# Adapter.net
KiCad netlist of a schematic drawn in Altium Designer
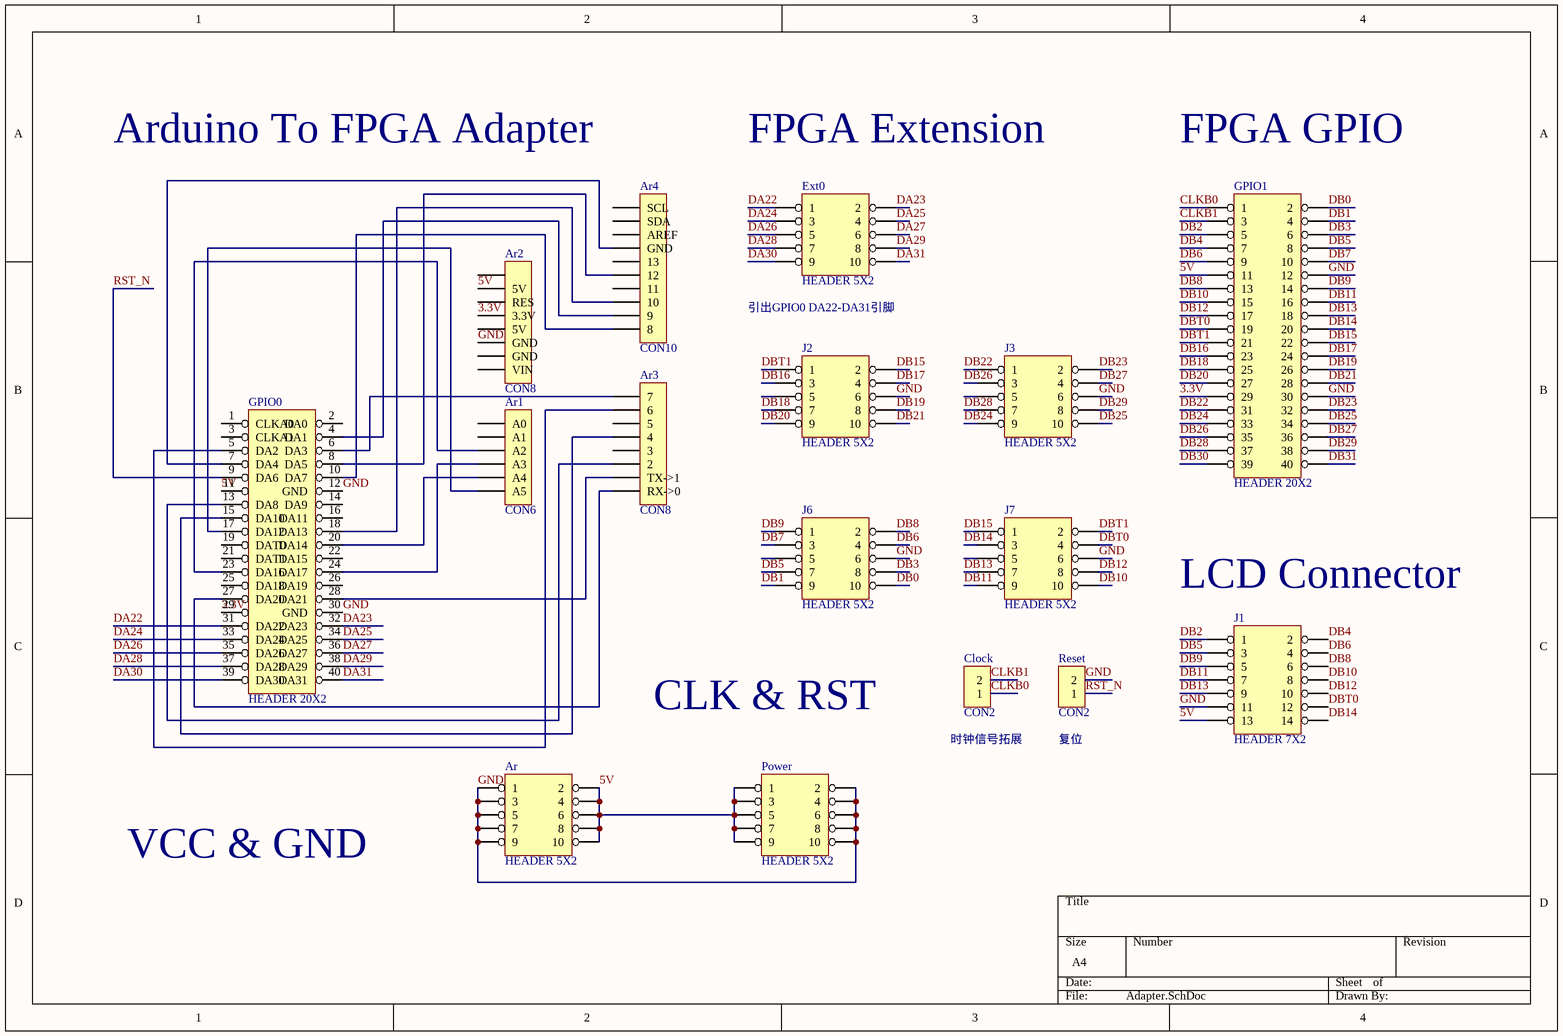
[diagram p0: Adapter.SchDoc]

(export (version "E")
  (design (tool "Eeschema 10.0.6"))
  (components
    (comp (ref "Ar")
      (value "HEADER 5X2")
      (footprint "HDR2X5")
      (libsource (lib "Miscellaneous Devices") (part "HEADER 5X2"))
    )
    (comp (ref "Ar1") (value "CON6") (footprint "HDR1X6") (libsource (lib "常用元件库") (part "CON6")))
    (comp (ref "Ar2") (value "CON8") (footprint "HDR1X8") (libsource (lib "常用元件库") (part "CON8")))
    (comp (ref "Ar3") (value "CON8") (footprint "HDR1X8") (libsource (lib "常用元件库") (part "CON8")))
    (comp (ref "Ar4") (value "CON10") (footprint "HDR1X10") (libsource (lib "常用元件库") (part "CON10")))
    (comp (ref "Clock")
      (value "CON2")
      (footprint "HDR1X2")
      (description "Connector")
      (libsource (lib "Miscellaneous Devices") (part "CON2"))
    )
    (comp (ref "Ext0")
      (value "HEADER 5X2")
      (footprint "HDR2X5")
      (libsource (lib "Miscellaneous Devices") (part "HEADER 5X2"))
    )
    (comp (ref "GPIO0")
      (value "HEADER 20X2")
      (footprint "Miscellaneous Connectors:HDR2X20")
      (libsource (lib "Miscellaneous Devices") (part "HEADER 20X2"))
    )
    (comp (ref "GPIO1")
      (value "HEADER 20X2")
      (footprint "Miscellaneous Connectors:HDR2X20")
      (libsource (lib "") (part "HEADER 20X2_1"))
    )
    (comp (ref "J1")
      (value "HEADER 7X2")
      (footprint "HDR2X7")
      (libsource (lib "Miscellaneous Devices") (part "HEADER 7X2"))
    )
    (comp (ref "J2")
      (value "HEADER 5X2")
      (footprint "HDR2X5")
      (libsource (lib "Miscellaneous Devices") (part "HEADER 5X2"))
    )
    (comp (ref "J3")
      (value "HEADER 5X2")
      (footprint "HDR2X5")
      (libsource (lib "Miscellaneous Devices") (part "HEADER 5X2"))
    )
    (comp (ref "J6")
      (value "HEADER 5X2")
      (footprint "HDR2X5")
      (libsource (lib "Miscellaneous Devices") (part "HEADER 5X2"))
    )
    (comp (ref "J7")
      (value "HEADER 5X2")
      (footprint "HDR2X5")
      (libsource (lib "Miscellaneous Devices") (part "HEADER 5X2"))
    )
    (comp (ref "Power")
      (value "HEADER 5X2")
      (footprint "HDR2X5")
      (libsource (lib "Miscellaneous Devices") (part "HEADER 5X2"))
    )
    (comp (ref "Reset")
      (value "CON2")
      (footprint "HDR1X2")
      (description "Connector")
      (libsource (lib "Miscellaneous Devices") (part "CON2"))
    )
  )
  (nets
    (net (code "1") (name "/3.3V") (class "Default")
      (node (ref "Ar2") (pin "4") (pinfunction "3.3V_4") (pintype "passive"))
      (node (ref "GPIO0") (pin "29") (pinfunction "29_29") (pintype "passive"))
      (node (ref "GPIO1") (pin "29") (pinfunction "29_29") (pintype "passive"))
    )
    (net (code "2") (name "/5V") (class "Default")
      (node (ref "Ar") (pin "10") (pinfunction "10_10") (pintype "passive"))
      (node (ref "Ar") (pin "2") (pinfunction "2_2") (pintype "passive"))
      (node (ref "Ar") (pin "4") (pinfunction "4_4") (pintype "passive"))
      (node (ref "Ar") (pin "6") (pinfunction "6_6") (pintype "passive"))
      (node (ref "Ar") (pin "8") (pinfunction "8_8") (pintype "passive"))
      (node (ref "Ar2") (pin "2") (pinfunction "5V_2") (pintype "passive"))
      (node (ref "GPIO0") (pin "11") (pinfunction "11_11") (pintype "passive"))
      (node (ref "GPIO1") (pin "11") (pinfunction "11_11") (pintype "passive"))
      (node (ref "J1") (pin "13") (pinfunction "13_13") (pintype "passive"))
      (node (ref "Power") (pin "1") (pinfunction "1_1") (pintype "passive"))
      (node (ref "Power") (pin "3") (pinfunction "3_3") (pintype "passive"))
      (node (ref "Power") (pin "5") (pinfunction "5_5") (pintype "passive"))
      (node (ref "Power") (pin "7") (pinfunction "7_7") (pintype "passive"))
      (node (ref "Power") (pin "9") (pinfunction "9_9") (pintype "passive"))
    )
    (net (code "3") (name "/CLKB0") (class "Default")
      (node (ref "Clock") (pin "1") (pinfunction "1_1") (pintype "passive"))
      (node (ref "GPIO1") (pin "1") (pinfunction "1_1") (pintype "passive"))
    )
    (net (code "4") (name "/CLKB1") (class "Default")
      (node (ref "Clock") (pin "2") (pinfunction "2_2") (pintype "passive"))
      (node (ref "GPIO1") (pin "3") (pinfunction "3_3") (pintype "passive"))
    )
    (net (code "5") (name "/DA22") (class "Default")
      (node (ref "Ext0") (pin "1") (pinfunction "1_1") (pintype "passive"))
      (node (ref "GPIO0") (pin "31") (pinfunction "DA22_31") (pintype "passive"))
    )
    (net (code "6") (name "/DA23") (class "Default")
      (node (ref "Ext0") (pin "2") (pinfunction "2_2") (pintype "passive"))
      (node (ref "GPIO0") (pin "32") (pinfunction "DA23_32") (pintype "passive"))
    )
    (net (code "7") (name "/DA24") (class "Default")
      (node (ref "Ext0") (pin "3") (pinfunction "3_3") (pintype "passive"))
      (node (ref "GPIO0") (pin "33") (pinfunction "DA24_33") (pintype "passive"))
    )
    (net (code "8") (name "/DA25") (class "Default")
      (node (ref "Ext0") (pin "4") (pinfunction "4_4") (pintype "passive"))
      (node (ref "GPIO0") (pin "34") (pinfunction "DA25_34") (pintype "passive"))
    )
    (net (code "9") (name "/DA26") (class "Default")
      (node (ref "Ext0") (pin "5") (pinfunction "5_5") (pintype "passive"))
      (node (ref "GPIO0") (pin "35") (pinfunction "DA26_35") (pintype "passive"))
    )
    (net (code "10") (name "/DA27") (class "Default")
      (node (ref "Ext0") (pin "6") (pinfunction "6_6") (pintype "passive"))
      (node (ref "GPIO0") (pin "36") (pinfunction "DA27_36") (pintype "passive"))
    )
    (net (code "11") (name "/DA28") (class "Default")
      (node (ref "Ext0") (pin "7") (pinfunction "7_7") (pintype "passive"))
      (node (ref "GPIO0") (pin "37") (pinfunction "DA28_37") (pintype "passive"))
    )
    (net (code "12") (name "/DA29") (class "Default")
      (node (ref "Ext0") (pin "8") (pinfunction "8_8") (pintype "passive"))
      (node (ref "GPIO0") (pin "38") (pinfunction "DA29_38") (pintype "passive"))
    )
    (net (code "13") (name "/DA30") (class "Default")
      (node (ref "Ext0") (pin "9") (pinfunction "9_9") (pintype "passive"))
      (node (ref "GPIO0") (pin "39") (pinfunction "DA30_39") (pintype "passive"))
    )
    (net (code "14") (name "/DA31") (class "Default")
      (node (ref "Ext0") (pin "10") (pinfunction "10_10") (pintype "passive"))
      (node (ref "GPIO0") (pin "40") (pinfunction "DA31_40") (pintype "passive"))
    )
    (net (code "15") (name "/DB0") (class "Default")
      (node (ref "GPIO1") (pin "2") (pinfunction "2_2") (pintype "passive"))
      (node (ref "J6") (pin "10") (pinfunction "10_10") (pintype "passive"))
    )
    (net (code "16") (name "/DB1") (class "Default")
      (node (ref "GPIO1") (pin "4") (pinfunction "4_4") (pintype "passive"))
      (node (ref "J6") (pin "9") (pinfunction "9_9") (pintype "passive"))
    )
    (net (code "17") (name "/DB2") (class "Default")
      (node (ref "GPIO1") (pin "5") (pinfunction "5_5") (pintype "passive"))
      (node (ref "J1") (pin "1") (pinfunction "1_1") (pintype "passive"))
    )
    (net (code "18") (name "/DB3") (class "Default")
      (node (ref "GPIO1") (pin "6") (pinfunction "6_6") (pintype "passive"))
      (node (ref "J6") (pin "8") (pinfunction "8_8") (pintype "passive"))
    )
    (net (code "19") (name "/DB4") (class "Default")
      (node (ref "GPIO1") (pin "7") (pinfunction "7_7") (pintype "passive"))
      (node (ref "J1") (pin "2") (pinfunction "2_2") (pintype "passive"))
    )
    (net (code "20") (name "/DB5") (class "Default")
      (node (ref "GPIO1") (pin "8") (pinfunction "8_8") (pintype "passive"))
      (node (ref "J1") (pin "3") (pinfunction "3_3") (pintype "passive"))
      (node (ref "J6") (pin "7") (pinfunction "7_7") (pintype "passive"))
    )
    (net (code "21") (name "/DB6") (class "Default")
      (node (ref "GPIO1") (pin "9") (pinfunction "9_9") (pintype "passive"))
      (node (ref "J1") (pin "4") (pinfunction "4_4") (pintype "passive"))
      (node (ref "J6") (pin "4") (pinfunction "4_4") (pintype "passive"))
    )
    (net (code "22") (name "/DB7") (class "Default")
      (node (ref "GPIO1") (pin "10") (pinfunction "10_10") (pintype "passive"))
      (node (ref "J6") (pin "3") (pinfunction "3_3") (pintype "passive"))
    )
    (net (code "23") (name "/DB8") (class "Default")
      (node (ref "GPIO1") (pin "13") (pinfunction "13_13") (pintype "passive"))
      (node (ref "J1") (pin "6") (pinfunction "6_6") (pintype "passive"))
      (node (ref "J6") (pin "2") (pinfunction "2_2") (pintype "passive"))
    )
    (net (code "24") (name "/DB9") (class "Default")
      (node (ref "GPIO1") (pin "14") (pinfunction "14_14") (pintype "passive"))
      (node (ref "J1") (pin "5") (pinfunction "5_5") (pintype "passive"))
      (node (ref "J6") (pin "1") (pinfunction "1_1") (pintype "passive"))
    )
    (net (code "25") (name "/DB10") (class "Default")
      (node (ref "GPIO1") (pin "15") (pinfunction "15_15") (pintype "passive"))
      (node (ref "J1") (pin "8") (pinfunction "8_8") (pintype "passive"))
      (node (ref "J7") (pin "10") (pinfunction "10_10") (pintype "passive"))
    )
    (net (code "26") (name "/DB11") (class "Default")
      (node (ref "GPIO1") (pin "16") (pinfunction "16_16") (pintype "passive"))
      (node (ref "J1") (pin "7") (pinfunction "7_7") (pintype "passive"))
      (node (ref "J7") (pin "9") (pinfunction "9_9") (pintype "passive"))
    )
    (net (code "27") (name "/DB12") (class "Default")
      (node (ref "GPIO1") (pin "17") (pinfunction "17_17") (pintype "passive"))
      (node (ref "J1") (pin "10") (pinfunction "10_10") (pintype "passive"))
      (node (ref "J7") (pin "8") (pinfunction "8_8") (pintype "passive"))
    )
    (net (code "28") (name "/DB13") (class "Default")
      (node (ref "GPIO1") (pin "18") (pinfunction "18_18") (pintype "passive"))
      (node (ref "J1") (pin "9") (pinfunction "9_9") (pintype "passive"))
      (node (ref "J7") (pin "7") (pinfunction "7_7") (pintype "passive"))
    )
    (net (code "29") (name "/DB14") (class "Default")
      (node (ref "GPIO1") (pin "20") (pinfunction "20_20") (pintype "passive"))
      (node (ref "J1") (pin "14") (pinfunction "14_14") (pintype "passive"))
      (node (ref "J7") (pin "3") (pinfunction "3_3") (pintype "passive"))
    )
    (net (code "30") (name "/DB15") (class "Default")
      (node (ref "GPIO1") (pin "22") (pinfunction "22_22") (pintype "passive"))
      (node (ref "J2") (pin "2") (pinfunction "2_2") (pintype "passive"))
      (node (ref "J7") (pin "1") (pinfunction "1_1") (pintype "passive"))
    )
    (net (code "31") (name "/DB16") (class "Default")
      (node (ref "GPIO1") (pin "23") (pinfunction "23_23") (pintype "passive"))
      (node (ref "J2") (pin "3") (pinfunction "3_3") (pintype "passive"))
    )
    (net (code "32") (name "/DB17") (class "Default")
      (node (ref "GPIO1") (pin "24") (pinfunction "24_24") (pintype "passive"))
      (node (ref "J2") (pin "4") (pinfunction "4_4") (pintype "passive"))
    )
    (net (code "33") (name "/DB18") (class "Default")
      (node (ref "GPIO1") (pin "25") (pinfunction "25_25") (pintype "passive"))
      (node (ref "J2") (pin "7") (pinfunction "7_7") (pintype "passive"))
    )
    (net (code "34") (name "/DB19") (class "Default")
      (node (ref "GPIO1") (pin "26") (pinfunction "26_26") (pintype "passive"))
      (node (ref "J2") (pin "8") (pinfunction "8_8") (pintype "passive"))
    )
    (net (code "35") (name "/DB20") (class "Default")
      (node (ref "GPIO1") (pin "27") (pinfunction "27_27") (pintype "passive"))
      (node (ref "J2") (pin "9") (pinfunction "9_9") (pintype "passive"))
    )
    (net (code "36") (name "/DB21") (class "Default")
      (node (ref "GPIO1") (pin "28") (pinfunction "28_28") (pintype "passive"))
      (node (ref "J2") (pin "10") (pinfunction "10_10") (pintype "passive"))
    )
    (net (code "37") (name "/DB22") (class "Default")
      (node (ref "GPIO1") (pin "31") (pinfunction "31_31") (pintype "passive"))
      (node (ref "J3") (pin "1") (pinfunction "1_1") (pintype "passive"))
    )
    (net (code "38") (name "/DB23") (class "Default")
      (node (ref "GPIO1") (pin "32") (pinfunction "32_32") (pintype "passive"))
      (node (ref "J3") (pin "2") (pinfunction "2_2") (pintype "passive"))
    )
    (net (code "39") (name "/DB24") (class "Default")
      (node (ref "GPIO1") (pin "33") (pinfunction "33_33") (pintype "passive"))
      (node (ref "J3") (pin "9") (pinfunction "9_9") (pintype "passive"))
    )
    (net (code "40") (name "/DB25") (class "Default")
      (node (ref "GPIO1") (pin "34") (pinfunction "34_34") (pintype "passive"))
      (node (ref "J3") (pin "10") (pinfunction "10_10") (pintype "passive"))
    )
    (net (code "41") (name "/DB26") (class "Default")
      (node (ref "GPIO1") (pin "35") (pinfunction "35_35") (pintype "passive"))
      (node (ref "J3") (pin "3") (pinfunction "3_3") (pintype "passive"))
    )
    (net (code "42") (name "/DB27") (class "Default")
      (node (ref "GPIO1") (pin "36") (pinfunction "36_36") (pintype "passive"))
      (node (ref "J3") (pin "4") (pinfunction "4_4") (pintype "passive"))
    )
    (net (code "43") (name "/DB28") (class "Default")
      (node (ref "GPIO1") (pin "37") (pinfunction "37_37") (pintype "passive"))
      (node (ref "J3") (pin "7") (pinfunction "7_7") (pintype "passive"))
    )
    (net (code "44") (name "/DB29") (class "Default")
      (node (ref "GPIO1") (pin "38") (pinfunction "38_38") (pintype "passive"))
      (node (ref "J3") (pin "8") (pinfunction "8_8") (pintype "passive"))
    )
    (net (code "45") (name "/DB30") (class "Default")
      (node (ref "GPIO1") (pin "39") (pinfunction "39_39") (pintype "passive"))
    )
    (net (code "46") (name "/DB31") (class "Default")
      (node (ref "GPIO1") (pin "40") (pinfunction "40_40") (pintype "passive"))
    )
    (net (code "47") (name "/DBT0") (class "Default")
      (node (ref "GPIO1") (pin "19") (pinfunction "19_19") (pintype "passive"))
      (node (ref "J1") (pin "12") (pinfunction "12_12") (pintype "passive"))
      (node (ref "J7") (pin "4") (pinfunction "4_4") (pintype "passive"))
    )
    (net (code "48") (name "/DBT1") (class "Default")
      (node (ref "GPIO1") (pin "21") (pinfunction "21_21") (pintype "passive"))
      (node (ref "J2") (pin "1") (pinfunction "1_1") (pintype "passive"))
      (node (ref "J7") (pin "2") (pinfunction "2_2") (pintype "passive"))
    )
    (net (code "49") (name "/GND") (class "Default")
      (node (ref "Ar") (pin "1") (pinfunction "1_1") (pintype "passive"))
      (node (ref "Ar") (pin "3") (pinfunction "3_3") (pintype "passive"))
      (node (ref "Ar") (pin "5") (pinfunction "5_5") (pintype "passive"))
      (node (ref "Ar") (pin "7") (pinfunction "7_7") (pintype "passive"))
      (node (ref "Ar") (pin "9") (pinfunction "9_9") (pintype "passive"))
      (node (ref "Ar2") (pin "6") (pinfunction "GND_6") (pintype "passive"))
      (node (ref "GPIO0") (pin "12") (pinfunction "GND_12") (pintype "passive"))
      (node (ref "GPIO0") (pin "30") (pinfunction "GND_30") (pintype "passive"))
      (node (ref "GPIO1") (pin "12") (pinfunction "12_12") (pintype "passive"))
      (node (ref "GPIO1") (pin "30") (pinfunction "30_30") (pintype "passive"))
      (node (ref "J1") (pin "11") (pinfunction "11_11") (pintype "passive"))
      (node (ref "J2") (pin "6") (pinfunction "6_6") (pintype "passive"))
      (node (ref "J3") (pin "6") (pinfunction "6_6") (pintype "passive"))
      (node (ref "J6") (pin "6") (pinfunction "6_6") (pintype "passive"))
      (node (ref "J7") (pin "6") (pinfunction "6_6") (pintype "passive"))
      (node (ref "Power") (pin "10") (pinfunction "10_10") (pintype "passive"))
      (node (ref "Power") (pin "2") (pinfunction "2_2") (pintype "passive"))
      (node (ref "Power") (pin "4") (pinfunction "4_4") (pintype "passive"))
      (node (ref "Power") (pin "6") (pinfunction "6_6") (pintype "passive"))
      (node (ref "Power") (pin "8") (pinfunction "8_8") (pintype "passive"))
      (node (ref "Reset") (pin "2") (pinfunction "2_2") (pintype "passive"))
    )
    (net (code "50") (name "/RST_N") (class "Default")
      (node (ref "GPIO0") (pin "9") (pinfunction "DA6_9") (pintype "passive"))
      (node (ref "Reset") (pin "1") (pinfunction "1_1") (pintype "passive"))
    )
    (net (code "51") (name "Net-(Ar1-A2)") (class "Default")
      (node (ref "Ar1") (pin "3") (pinfunction "A2_3") (pintype "passive"))
      (node (ref "GPIO0") (pin "23") (pinfunction "DA16_23") (pintype "passive"))
    )
    (net (code "52") (name "Net-(Ar1-A3)") (class "Default")
      (node (ref "Ar1") (pin "4") (pinfunction "A3_4") (pintype "passive"))
      (node (ref "GPIO0") (pin "24") (pinfunction "DA17_24") (pintype "passive"))
    )
    (net (code "53") (name "Net-(Ar1-A4)") (class "Default")
      (node (ref "Ar1") (pin "5") (pinfunction "A4_5") (pintype "passive"))
      (node (ref "GPIO0") (pin "20") (pinfunction "DA14_20") (pintype "passive"))
    )
    (net (code "54") (name "Net-(Ar1-A5)") (class "Default")
      (node (ref "Ar1") (pin "6") (pinfunction "A5_6") (pintype "passive"))
      (node (ref "GPIO0") (pin "17") (pinfunction "DA12_17") (pintype "passive"))
    )
    (net (code "55") (name "Net-(Ar3-3.3V)") (class "Default")
      (node (ref "Ar3") (pin "4") (pinfunction "3.3V_4") (pintype "passive"))
      (node (ref "GPIO0") (pin "15") (pinfunction "DA10_15") (pintype "passive"))
    )
    (net (code "56") (name "Net-(Ar3-VIN)") (class "Default")
      (node (ref "Ar3") (pin "8") (pinfunction "VIN_8") (pintype "passive"))
      (node (ref "GPIO0") (pin "27") (pinfunction "DA20_27") (pintype "passive"))
    )
    (net (code "57") (name "Net-(Ar4-8)") (class "Default")
      (node (ref "Ar4") (pin "10") (pinfunction "8_10") (pintype "passive"))
      (node (ref "GPIO0") (pin "10") (pinfunction "DA7_10") (pintype "passive"))
    )
    (net (code "58") (name "Net-(Ar4-10)") (class "Default")
      (node (ref "Ar4") (pin "8") (pinfunction "10_8") (pintype "passive"))
      (node (ref "GPIO0") (pin "18") (pinfunction "DA13_18") (pintype "passive"))
    )
    (net (code "59") (name "Net-(Ar4-12)") (class "Default")
      (node (ref "Ar4") (pin "6") (pinfunction "12_6") (pintype "passive"))
      (node (ref "GPIO0") (pin "8") (pinfunction "DA5_8") (pintype "passive"))
    )
    (net (code "60") (name "Net-(Ar4-GND)") (class "Default")
      (node (ref "Ar4") (pin "4") (pinfunction "GND_4") (pintype "passive"))
      (node (ref "GPIO0") (pin "7") (pinfunction "DA4_7") (pintype "passive"))
    )
    (net (code "61") (name "Net-(GPIO0-DA1)") (class "Default")
      (node (ref "Ar4") (pin "9") (pinfunction "9_9") (pintype "passive"))
      (node (ref "GPIO0") (pin "4") (pinfunction "DA1_4") (pintype "passive"))
    )
    (net (code "62") (name "Net-(GPIO0-DA2)") (class "Default")
      (node (ref "Ar3") (pin "2") (pinfunction "5V_2") (pintype "passive"))
      (node (ref "GPIO0") (pin "5") (pinfunction "DA2_5") (pintype "passive"))
    )
    (net (code "63") (name "Net-(GPIO0-DA3)") (class "Default")
      (node (ref "Ar3") (pin "1") (pinfunction "1_1") (pintype "passive"))
      (node (ref "GPIO0") (pin "6") (pinfunction "DA3_6") (pintype "passive"))
    )
    (net (code "64") (name "Net-(GPIO0-DA8)") (class "Default")
      (node (ref "Ar3") (pin "6") (pinfunction "GND_6") (pintype "passive"))
      (node (ref "GPIO0") (pin "13") (pinfunction "DA8_13") (pintype "passive"))
    )
    (net (code "65") (name "Net-(GPIO0-DA21)") (class "Default")
      (node (ref "Ar3") (pin "7") (pinfunction "GND_7") (pintype "passive"))
      (node (ref "GPIO0") (pin "28") (pinfunction "DA21_28") (pintype "passive"))
    )
    (net (code "66") (name "unconnected-(Ar1-A0-Pad1)") (class "Default")
      (node (ref "Ar1") (pin "1") (pinfunction "A0_1") (pintype "passive"))
    )
    (net (code "67") (name "unconnected-(Ar1-A1-Pad2)") (class "Default")
      (node (ref "Ar1") (pin "2") (pinfunction "A1_2") (pintype "passive"))
    )
    (net (code "68") (name "unconnected-(Ar2-5V-Pad5)") (class "Default")
      (node (ref "Ar2") (pin "5") (pinfunction "5V_5") (pintype "passive"))
    )
    (net (code "69") (name "unconnected-(Ar2-GND-Pad7)") (class "Default")
      (node (ref "Ar2") (pin "7") (pinfunction "GND_7") (pintype "passive"))
    )
    (net (code "70") (name "unconnected-(Ar2-Pad1)") (class "Default")
      (node (ref "Ar2") (pin "1") (pinfunction "1_1") (pintype "passive"))
    )
    (net (code "71") (name "unconnected-(Ar2-RES-Pad3)") (class "Default")
      (node (ref "Ar2") (pin "3") (pinfunction "RES_3") (pintype "passive"))
    )
    (net (code "72") (name "unconnected-(Ar2-VIN-Pad8)") (class "Default")
      (node (ref "Ar2") (pin "8") (pinfunction "VIN_8") (pintype "passive"))
    )
    (net (code "73") (name "unconnected-(Ar3-5V-Pad5)") (class "Default")
      (node (ref "Ar3") (pin "5") (pinfunction "5V_5") (pintype "passive"))
    )
    (net (code "74") (name "unconnected-(Ar3-RES-Pad3)") (class "Default")
      (node (ref "Ar3") (pin "3") (pinfunction "RES_3") (pintype "passive"))
    )
    (net (code "75") (name "unconnected-(Ar4-11-Pad7)") (class "Default")
      (node (ref "Ar4") (pin "7") (pinfunction "11_7") (pintype "passive"))
    )
    (net (code "76") (name "unconnected-(Ar4-13-Pad5)") (class "Default")
      (node (ref "Ar4") (pin "5") (pinfunction "13_5") (pintype "passive"))
    )
    (net (code "77") (name "unconnected-(Ar4-AREF-Pad3)") (class "Default")
      (node (ref "Ar4") (pin "3") (pinfunction "AREF_3") (pintype "passive"))
    )
    (net (code "78") (name "unconnected-(Ar4-SCL-Pad1)") (class "Default")
      (node (ref "Ar4") (pin "1") (pinfunction "SCL_1") (pintype "passive"))
    )
    (net (code "79") (name "unconnected-(Ar4-SDA-Pad2)") (class "Default")
      (node (ref "Ar4") (pin "2") (pinfunction "SDA_2") (pintype "passive"))
    )
    (net (code "80") (name "unconnected-(GPIO0-CLKA0-Pad1)") (class "Default")
      (node (ref "GPIO0") (pin "1") (pinfunction "CLKA0_1") (pintype "passive"))
    )
    (net (code "81") (name "unconnected-(GPIO0-CLKA1-Pad3)") (class "Default")
      (node (ref "GPIO0") (pin "3") (pinfunction "CLKA1_3") (pintype "passive"))
    )
    (net (code "82") (name "unconnected-(GPIO0-DA0-Pad2)") (class "Default")
      (node (ref "GPIO0") (pin "2") (pinfunction "DA0_2") (pintype "passive"))
    )
    (net (code "83") (name "unconnected-(GPIO0-DA9-Pad14)") (class "Default")
      (node (ref "GPIO0") (pin "14") (pinfunction "DA9_14") (pintype "passive"))
    )
    (net (code "84") (name "unconnected-(GPIO0-DA11-Pad16)") (class "Default")
      (node (ref "GPIO0") (pin "16") (pinfunction "DA11_16") (pintype "passive"))
    )
    (net (code "85") (name "unconnected-(GPIO0-DA15-Pad22)") (class "Default")
      (node (ref "GPIO0") (pin "22") (pinfunction "DA15_22") (pintype "passive"))
    )
    (net (code "86") (name "unconnected-(GPIO0-DA18-Pad25)") (class "Default")
      (node (ref "GPIO0") (pin "25") (pinfunction "DA18_25") (pintype "passive"))
    )
    (net (code "87") (name "unconnected-(GPIO0-DA19-Pad26)") (class "Default")
      (node (ref "GPIO0") (pin "26") (pinfunction "DA19_26") (pintype "passive"))
    )
    (net (code "88") (name "unconnected-(GPIO0-DAT0-Pad19)") (class "Default")
      (node (ref "GPIO0") (pin "19") (pinfunction "DAT0_19") (pintype "passive"))
    )
    (net (code "89") (name "unconnected-(GPIO0-DAT1-Pad21)") (class "Default")
      (node (ref "GPIO0") (pin "21") (pinfunction "DAT1_21") (pintype "passive"))
    )
    (net (code "90") (name "unconnected-(J2-Pad5)") (class "Default")
      (node (ref "J2") (pin "5") (pinfunction "5_5") (pintype "passive"))
    )
    (net (code "91") (name "unconnected-(J3-Pad5)") (class "Default")
      (node (ref "J3") (pin "5") (pinfunction "5_5") (pintype "passive"))
    )
    (net (code "92") (name "unconnected-(J6-Pad5)") (class "Default")
      (node (ref "J6") (pin "5") (pinfunction "5_5") (pintype "passive"))
    )
    (net (code "93") (name "unconnected-(J7-Pad5)") (class "Default")
      (node (ref "J7") (pin "5") (pinfunction "5_5") (pintype "passive"))
    )
  )
)
